# Shield.net
KiCad netlist of a schematic drawn in Altium Designer
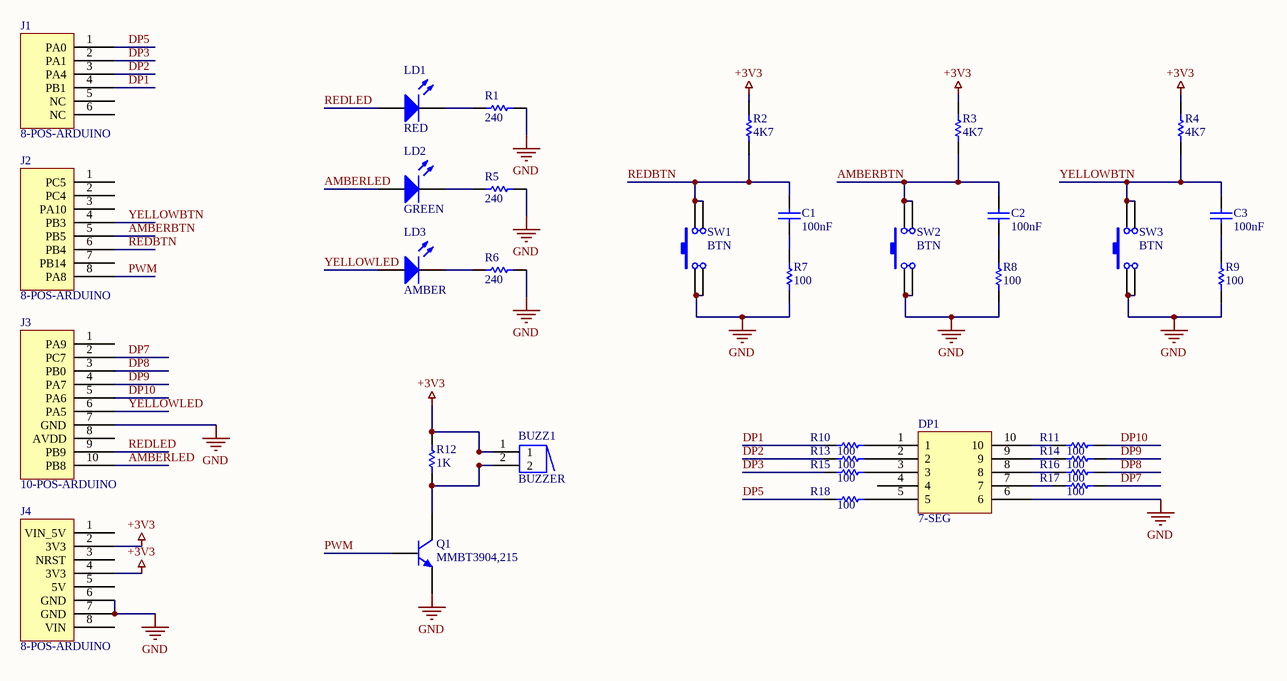
[diagram p0: Shield.SchDoc]

(export (version "E")
  (design (tool "Eeschema 10.0.6"))
  (components
    (comp (ref "BUZZ1")
      (value "BUZZER")
      (footprint "Buzzer")
      (description "AUDIO PIEZO TRANSDUCER 30V TH")
      (fields (field (name "MANUFACTURER") "TDK") (field (name "MANUFACTURER PART NUMBER") "PS1240P02BT"))
      (libsource (lib "Shield") (part "PS1240P02BT"))
    )
    (comp (ref "C1")
      (value "100nF")
      (footprint "CAPC3216X12N")
      (description "CAP CER 0.1UF 50V X7R 1206")
      (fields
        (field (name "MANUFACTURER") "Yageo")
        (field (name "MANUFACTURER PART NUMBER") "CC1206KRX7R9BB104")
      )
      (libsource (lib "Shield") (part "CC1206KRX7R9BB104"))
    )
    (comp (ref "C2")
      (value "100nF")
      (footprint "CAPC3216X12N")
      (description "CAP CER 0.1UF 50V X7R 1206")
      (fields
        (field (name "MANUFACTURER") "Yageo")
        (field (name "MANUFACTURER PART NUMBER") "CC1206KRX7R9BB104")
      )
      (libsource (lib "Shield") (part "CC1206KRX7R9BB104"))
    )
    (comp (ref "C3")
      (value "100nF")
      (footprint "CAPC3216X12N")
      (description "CAP CER 0.1UF 50V X7R 1206")
      (fields
        (field (name "MANUFACTURER") "Yageo")
        (field (name "MANUFACTURER PART NUMBER") "CC1206KRX7R9BB104")
      )
      (libsource (lib "Shield") (part "CC1206KRX7R9BB104"))
    )
    (comp (ref "DP1")
      (value "7-SEG")
      (footprint "7-seg-display")
      (fields
        (field (name "MANUFACTURER") "Inolux")
        (field (name "MANUFACTURER PART NUMBER") "INND-TS40YGCB")
      )
      (libsource (lib "Shield") (part "INND-TS40YGCB"))
    )
    (comp (ref "J1")
      (value "8-POS-ARDUINO")
      (footprint "PIN 6")
      (description "Conn Header Vert 6POS 2.54MM")
      (fields
        (field (name "MANUFACTURER") "Sullins")
        (field (name "MANUFACTURER PART NUMBER") "PREC006SABN-RC")
      )
      (libsource (lib "Shield") (part "PREC006SABN-RC"))
    )
    (comp (ref "J2")
      (value "8-POS-ARDUINO")
      (footprint "PIN 8")
      (description "CONN HEADER VERT 8POS 2.54MM")
      (fields
        (field (name "MANUFACTURER") "Sullins")
        (field (name "MANUFACTURER PART NUMBER") "PREC008SAAN-RC")
      )
      (libsource (lib "Shield") (part "PREC008SAAN-RC"))
    )
    (comp (ref "J3")
      (value "10-POS-ARDUINO")
      (footprint "PIN 10")
      (description "CONN HEADER .100\" SNGL STR 10POS")
      (fields
        (field (name "MANUFACTURER") "Sullins")
        (field (name "MANUFACTURER PART NUMBER") "PREC010SAAN-RC")
      )
      (libsource (lib "Shield") (part "PREC010SAAN-RC"))
    )
    (comp (ref "J4")
      (value "8-POS-ARDUINO")
      (footprint "PIN 8")
      (description "CONN HEADER VERT 8POS 2.54MM")
      (fields
        (field (name "MANUFACTURER") "Sullins")
        (field (name "MANUFACTURER PART NUMBER") "PREC008SAAN-RC")
      )
      (libsource (lib "Shield") (part "PREC008SAAN-RC (2)"))
    )
    (comp (ref "LD1")
      (value "RED")
      (footprint "DIOC3216X21N")
      (description "LED Uni-Color Red 660nm 2-Pin Chip LED T/R")
      (fields
        (field (name "MANUFACTURER") "Vishay Lite-On")
        (field (name "MANUFACTURER PART NUMBER") "LTST-C150CKT")
      )
      (libsource (lib "Shield") (part "LTST-C150CKT"))
    )
    (comp (ref "LD2")
      (value "GREEN")
      (footprint "DIOC3216X21N")
      (description "LED GREEN CLEAR 1206 SMD")
      (fields
        (field (name "MANUFACTURER") "Vishay Lite-On")
        (field (name "MANUFACTURER PART NUMBER") "LTST-C150GKT")
      )
      (libsource (lib "Shield") (part "LTST-C150GKT"))
    )
    (comp (ref "LD3")
      (value "AMBER")
      (footprint "DIOC3216X21N")
      (description "LED AMBER CLEAR 1206 SMD")
      (fields
        (field (name "MANUFACTURER") "Vishay Lite-On")
        (field (name "MANUFACTURER PART NUMBER") "LTST-C150AKT")
      )
      (libsource (lib "Shield") (part "LTST-C150AKT"))
    )
    (comp (ref "Q1")
      (value "MMBT3904,215")
      (footprint "SOT95P230X110-3N")
      (description "TRANS NPN 40V 0.2A SOT23")
      (fields (field (name "MANUFACTURER") "Nexperia"))
      (libsource (lib "Shield") (part "MMBT3904,215"))
    )
    (comp (ref "R1")
      (value "240")
      (footprint "RESC3115X06N")
      (description "Res Thick Film 1206 240 Ohm 1% 0.25W(1/4W) ±100ppm/C Molded SMD Automotive T/R")
      (fields
        (field (name "MANUFACTURER") "Stackpole Electronics")
        (field (name "MANUFACTURER PART NUMBER") "RMCF1206FT240R")
      )
      (libsource (lib "Shield") (part "RMCF1206FT240R"))
    )
    (comp (ref "R2")
      (value "4K7")
      (footprint "RESC3115X06N")
      (description "RES SMD 4.7K OHM 1% 1/4W 1206")
      (fields
        (field (name "MANUFACTURER") "Stackpole Electronics")
        (field (name "MANUFACTURER PART NUMBER") "RMCF1206FT4K70")
      )
      (libsource (lib "Shield") (part "RMCF1206FT4K70"))
    )
    (comp (ref "R3")
      (value "4K7")
      (footprint "RESC3115X06N")
      (description "RES SMD 4.7K OHM 1% 1/4W 1206")
      (fields
        (field (name "MANUFACTURER") "Stackpole Electronics")
        (field (name "MANUFACTURER PART NUMBER") "RMCF1206FT4K70")
      )
      (libsource (lib "Shield") (part "RMCF1206FT4K70"))
    )
    (comp (ref "R4")
      (value "4K7")
      (footprint "RESC3115X06N")
      (description "RES SMD 4.7K OHM 1% 1/4W 1206")
      (fields
        (field (name "MANUFACTURER") "Stackpole Electronics")
        (field (name "MANUFACTURER PART NUMBER") "RMCF1206FT4K70")
      )
      (libsource (lib "Shield") (part "RMCF1206FT4K70"))
    )
    (comp (ref "R5")
      (value "240")
      (footprint "RESC3115X06N")
      (description "Res Thick Film 1206 240 Ohm 1% 0.25W(1/4W) ±100ppm/C Molded SMD Automotive T/R")
      (fields
        (field (name "MANUFACTURER") "Stackpole Electronics")
        (field (name "MANUFACTURER PART NUMBER") "RMCF1206FT240R")
      )
      (libsource (lib "Shield") (part "RMCF1206FT240R"))
    )
    (comp (ref "R6")
      (value "240")
      (footprint "RESC3115X06N")
      (description "Res Thick Film 1206 240 Ohm 1% 0.25W(1/4W) ±100ppm/C Molded SMD Automotive T/R")
      (fields
        (field (name "MANUFACTURER") "Stackpole Electronics")
        (field (name "MANUFACTURER PART NUMBER") "RMCF1206FT240R")
      )
      (libsource (lib "Shield") (part "RMCF1206FT240R"))
    )
    (comp (ref "R7")
      (value "100")
      (footprint "RESC3115X06N")
      (description "RES 100 OHM 1% 1/4W 1206")
      (fields
        (field (name "MANUFACTURER") "Stackpole Electronics")
        (field (name "MANUFACTURER PART NUMBER") "RMCF1206FT100R")
      )
      (libsource (lib "Shield") (part "RMCF1206FT100R"))
    )
    (comp (ref "R8")
      (value "100")
      (footprint "RESC3115X06N")
      (description "RES 100 OHM 1% 1/4W 1206")
      (fields
        (field (name "MANUFACTURER") "Stackpole Electronics")
        (field (name "MANUFACTURER PART NUMBER") "RMCF1206FT100R")
      )
      (libsource (lib "Shield") (part "RMCF1206FT100R"))
    )
    (comp (ref "R9")
      (value "100")
      (footprint "RESC3115X06N")
      (description "RES 100 OHM 1% 1/4W 1206")
      (fields
        (field (name "MANUFACTURER") "Stackpole Electronics")
        (field (name "MANUFACTURER PART NUMBER") "RMCF1206FT100R")
      )
      (libsource (lib "Shield") (part "RMCF1206FT100R"))
    )
    (comp (ref "R10")
      (value "100")
      (footprint "RESC3115X06N")
      (description "RES 100 OHM 1% 1/4W 1206")
      (fields
        (field (name "MANUFACTURER") "Stackpole Electronics")
        (field (name "MANUFACTURER PART NUMBER") "RMCF1206FT100R")
      )
      (libsource (lib "Shield") (part "RMCF1206FT100R"))
    )
    (comp (ref "R11")
      (value "100")
      (footprint "RESC3115X06N")
      (description "RES 100 OHM 1% 1/4W 1206")
      (fields
        (field (name "MANUFACTURER") "Stackpole Electronics")
        (field (name "MANUFACTURER PART NUMBER") "RMCF1206FT100R")
      )
      (libsource (lib "Shield") (part "RMCF1206FT100R"))
    )
    (comp (ref "R12")
      (value "1K")
      (footprint "RESC3115X06N")
      (description "RES 1K OHM 1% 1/2W 1206")
      (fields
        (field (name "MANUFACTURER") "Stackpole Electronics")
        (field (name "MANUFACTURER PART NUMBER") "RNCP1206FTD1K00")
      )
      (libsource (lib "Shield") (part "RNCP1206FTD1K00"))
    )
    (comp (ref "R13")
      (value "100")
      (footprint "RESC3115X06N")
      (description "RES 100 OHM 1% 1/4W 1206")
      (fields
        (field (name "MANUFACTURER") "Stackpole Electronics")
        (field (name "MANUFACTURER PART NUMBER") "RMCF1206FT100R")
      )
      (libsource (lib "Shield") (part "RMCF1206FT100R"))
    )
    (comp (ref "R14")
      (value "100")
      (footprint "RESC3115X06N")
      (description "RES 100 OHM 1% 1/4W 1206")
      (fields
        (field (name "MANUFACTURER") "Stackpole Electronics")
        (field (name "MANUFACTURER PART NUMBER") "RMCF1206FT100R")
      )
      (libsource (lib "Shield") (part "RMCF1206FT100R"))
    )
    (comp (ref "R15")
      (value "100")
      (footprint "RESC3115X06N")
      (description "RES 100 OHM 1% 1/4W 1206")
      (fields
        (field (name "MANUFACTURER") "Stackpole Electronics")
        (field (name "MANUFACTURER PART NUMBER") "RMCF1206FT100R")
      )
      (libsource (lib "Shield") (part "RMCF1206FT100R"))
    )
    (comp (ref "R16")
      (value "100")
      (footprint "RESC3115X06N")
      (description "RES 100 OHM 1% 1/4W 1206")
      (fields
        (field (name "MANUFACTURER") "Stackpole Electronics")
        (field (name "MANUFACTURER PART NUMBER") "RMCF1206FT100R")
      )
      (libsource (lib "Shield") (part "RMCF1206FT100R"))
    )
    (comp (ref "R17")
      (value "100")
      (footprint "RESC3115X06N")
      (description "RES 100 OHM 1% 1/4W 1206")
      (fields
        (field (name "MANUFACTURER") "Stackpole Electronics")
        (field (name "MANUFACTURER PART NUMBER") "RMCF1206FT100R")
      )
      (libsource (lib "Shield") (part "RMCF1206FT100R"))
    )
    (comp (ref "R18")
      (value "100")
      (footprint "RESC3115X06N")
      (description "RES 100 OHM 1% 1/4W 1206")
      (fields
        (field (name "MANUFACTURER") "Stackpole Electronics")
        (field (name "MANUFACTURER PART NUMBER") "RMCF1206FT100R")
      )
      (libsource (lib "Shield") (part "RMCF1206FT100R"))
    )
    (comp (ref "SW1")
      (value "BTN")
      (footprint "Button")
      (description "INWALL LENS COVER , WHITE , 6 (")
      (fields
        (field (name "MANUFACTURER") "ITT C&K")
        (field (name "MANUFACTURER PART NUMBER") "PTS647SK70SMTR2LFS")
      )
      (libsource (lib "Shield") (part "PTS647SK70SMTR2LFS"))
    )
    (comp (ref "SW2")
      (value "BTN")
      (footprint "Button")
      (description "INWALL LENS COVER , WHITE , 6 (")
      (fields
        (field (name "MANUFACTURER") "ITT C&K")
        (field (name "MANUFACTURER PART NUMBER") "PTS647SK70SMTR2LFS")
      )
      (libsource (lib "Shield") (part "PTS647SK70SMTR2LFS"))
    )
    (comp (ref "SW3")
      (value "BTN")
      (footprint "Button")
      (description "INWALL LENS COVER , WHITE , 6 (")
      (fields
        (field (name "MANUFACTURER") "ITT C&K")
        (field (name "MANUFACTURER PART NUMBER") "PTS647SK70SMTR2LFS")
      )
      (libsource (lib "Shield") (part "PTS647SK70SMTR2LFS"))
    )
  )
  (nets
    (net (code "1") (name "+3V3") (class "Default")
      (node (ref "BUZZ1") (pin "1") (pinfunction "1_1") (pintype "passive"))
      (node (ref "J4") (pin "2") (pinfunction "3V3_2") (pintype "passive"))
      (node (ref "J4") (pin "4") (pinfunction "3V3_4") (pintype "passive"))
      (node (ref "R12") (pin "2") (pinfunction "2_2") (pintype "passive"))
      (node (ref "R2") (pin "2") (pinfunction "2_2") (pintype "passive"))
      (node (ref "R3") (pin "2") (pinfunction "2_2") (pintype "passive"))
      (node (ref "R4") (pin "2") (pinfunction "2_2") (pintype "passive"))
    )
    (net (code "2") (name "/AMBERBTN") (class "Default")
      (node (ref "C2") (pin "2") (pinfunction "2_2") (pintype "passive"))
      (node (ref "J2") (pin "5") (pinfunction "PB5_5") (pintype "passive"))
      (node (ref "R3") (pin "1") (pinfunction "1_1") (pintype "passive"))
      (node (ref "SW2") (pin "3") (pinfunction "2_3") (pintype "passive"))
      (node (ref "SW2") (pin "4") (pinfunction "3_4") (pintype "passive"))
    )
    (net (code "3") (name "/AMBERLED") (class "Default")
      (node (ref "J3") (pin "10") (pinfunction "PB8_10") (pintype "passive"))
      (node (ref "LD2") (pin "1") (pinfunction "A_1") (pintype "passive"))
    )
    (net (code "4") (name "/DP1") (class "Default")
      (node (ref "J1") (pin "4") (pinfunction "PB1_4") (pintype "passive"))
      (node (ref "R10") (pin "2") (pinfunction "2_2") (pintype "passive"))
    )
    (net (code "5") (name "/DP2") (class "Default")
      (node (ref "J1") (pin "3") (pinfunction "PA4_3") (pintype "passive"))
      (node (ref "R13") (pin "2") (pinfunction "2_2") (pintype "passive"))
    )
    (net (code "6") (name "/DP3") (class "Default")
      (node (ref "J1") (pin "2") (pinfunction "PA1_2") (pintype "passive"))
      (node (ref "R15") (pin "2") (pinfunction "2_2") (pintype "passive"))
    )
    (net (code "7") (name "/DP5") (class "Default")
      (node (ref "J1") (pin "1") (pinfunction "PA0_1") (pintype "passive"))
      (node (ref "R18") (pin "2") (pinfunction "2_2") (pintype "passive"))
    )
    (net (code "8") (name "/DP7") (class "Default")
      (node (ref "J3") (pin "2") (pinfunction "PC7_2") (pintype "passive"))
      (node (ref "R17") (pin "1") (pinfunction "1_1") (pintype "passive"))
    )
    (net (code "9") (name "/DP8") (class "Default")
      (node (ref "J3") (pin "3") (pinfunction "PB0_3") (pintype "passive"))
      (node (ref "R16") (pin "1") (pinfunction "1_1") (pintype "passive"))
    )
    (net (code "10") (name "/DP9") (class "Default")
      (node (ref "J3") (pin "4") (pinfunction "PA7_4") (pintype "passive"))
      (node (ref "R14") (pin "1") (pinfunction "1_1") (pintype "passive"))
    )
    (net (code "11") (name "/DP10") (class "Default")
      (node (ref "J3") (pin "5") (pinfunction "PA6_5") (pintype "passive"))
      (node (ref "R11") (pin "1") (pinfunction "1_1") (pintype "passive"))
    )
    (net (code "12") (name "/PWM") (class "Default")
      (node (ref "J2") (pin "8") (pinfunction "PA8_8") (pintype "passive"))
      (node (ref "Q1") (pin "1") (pinfunction "B_1") (pintype "passive"))
    )
    (net (code "13") (name "/REDBTN") (class "Default")
      (node (ref "C1") (pin "2") (pinfunction "2_2") (pintype "passive"))
      (node (ref "J2") (pin "6") (pinfunction "PB4_6") (pintype "passive"))
      (node (ref "R2") (pin "1") (pinfunction "1_1") (pintype "passive"))
      (node (ref "SW1") (pin "3") (pinfunction "2_3") (pintype "passive"))
      (node (ref "SW1") (pin "4") (pinfunction "3_4") (pintype "passive"))
    )
    (net (code "14") (name "/REDLED") (class "Default")
      (node (ref "J3") (pin "9") (pinfunction "PB9_9") (pintype "passive"))
      (node (ref "LD1") (pin "1") (pinfunction "A_1") (pintype "passive"))
    )
    (net (code "15") (name "/YELLOWBTN") (class "Default")
      (node (ref "C3") (pin "2") (pinfunction "2_2") (pintype "passive"))
      (node (ref "J2") (pin "4") (pinfunction "PB3_4") (pintype "passive"))
      (node (ref "R4") (pin "1") (pinfunction "1_1") (pintype "passive"))
      (node (ref "SW3") (pin "3") (pinfunction "2_3") (pintype "passive"))
      (node (ref "SW3") (pin "4") (pinfunction "3_4") (pintype "passive"))
    )
    (net (code "16") (name "/YELLOWLED") (class "Default")
      (node (ref "J3") (pin "6") (pinfunction "PA5_6") (pintype "passive"))
      (node (ref "LD3") (pin "1") (pinfunction "A_1") (pintype "passive"))
    )
    (net (code "17") (name "GND") (class "Default")
      (node (ref "DP1") (pin "6") (pinfunction "6_6") (pintype "passive"))
      (node (ref "J3") (pin "7") (pinfunction "GND_7") (pintype "passive"))
      (node (ref "J4") (pin "6") (pinfunction "GND_6") (pintype "passive"))
      (node (ref "J4") (pin "7") (pinfunction "GND_7") (pintype "passive"))
      (node (ref "Q1") (pin "2") (pinfunction "E_2") (pintype "passive"))
      (node (ref "R1") (pin "2") (pinfunction "2_2") (pintype "passive"))
      (node (ref "R5") (pin "2") (pinfunction "2_2") (pintype "passive"))
      (node (ref "R6") (pin "2") (pinfunction "2_2") (pintype "passive"))
      (node (ref "R7") (pin "1") (pinfunction "1_1") (pintype "passive"))
      (node (ref "R8") (pin "1") (pinfunction "1_1") (pintype "passive"))
      (node (ref "R9") (pin "1") (pinfunction "1_1") (pintype "passive"))
      (node (ref "SW1") (pin "1") (pinfunction "1_1") (pintype "passive"))
      (node (ref "SW1") (pin "2") (pinfunction "1_2") (pintype "passive"))
      (node (ref "SW2") (pin "1") (pinfunction "1_1") (pintype "passive"))
      (node (ref "SW2") (pin "2") (pinfunction "1_2") (pintype "passive"))
      (node (ref "SW3") (pin "1") (pinfunction "1_1") (pintype "passive"))
      (node (ref "SW3") (pin "2") (pinfunction "1_2") (pintype "passive"))
    )
    (net (code "18") (name "Net-(C1-Pad1)") (class "Default")
      (node (ref "C1") (pin "1") (pinfunction "1_1") (pintype "passive"))
      (node (ref "R7") (pin "2") (pinfunction "2_2") (pintype "passive"))
    )
    (net (code "19") (name "Net-(C2-Pad1)") (class "Default")
      (node (ref "C2") (pin "1") (pinfunction "1_1") (pintype "passive"))
      (node (ref "R8") (pin "2") (pinfunction "2_2") (pintype "passive"))
    )
    (net (code "20") (name "Net-(C3-Pad1)") (class "Default")
      (node (ref "C3") (pin "1") (pinfunction "1_1") (pintype "passive"))
      (node (ref "R9") (pin "2") (pinfunction "2_2") (pintype "passive"))
    )
    (net (code "21") (name "Net-(DP1-Pad1)") (class "Default")
      (node (ref "DP1") (pin "1") (pinfunction "1_1") (pintype "passive"))
      (node (ref "R10") (pin "1") (pinfunction "1_1") (pintype "passive"))
    )
    (net (code "22") (name "Net-(DP1-Pad2)") (class "Default")
      (node (ref "DP1") (pin "2") (pinfunction "2_2") (pintype "passive"))
      (node (ref "R13") (pin "1") (pinfunction "1_1") (pintype "passive"))
    )
    (net (code "23") (name "Net-(DP1-Pad3)") (class "Default")
      (node (ref "DP1") (pin "3") (pinfunction "3_3") (pintype "passive"))
      (node (ref "R15") (pin "1") (pinfunction "1_1") (pintype "passive"))
    )
    (net (code "24") (name "Net-(DP1-Pad5)") (class "Default")
      (node (ref "DP1") (pin "5") (pinfunction "5_5") (pintype "passive"))
      (node (ref "R18") (pin "1") (pinfunction "1_1") (pintype "passive"))
    )
    (net (code "25") (name "Net-(DP1-Pad7)") (class "Default")
      (node (ref "DP1") (pin "7") (pinfunction "7_7") (pintype "passive"))
      (node (ref "R17") (pin "2") (pinfunction "2_2") (pintype "passive"))
    )
    (net (code "26") (name "Net-(DP1-Pad8)") (class "Default")
      (node (ref "DP1") (pin "8") (pinfunction "8_8") (pintype "passive"))
      (node (ref "R16") (pin "2") (pinfunction "2_2") (pintype "passive"))
    )
    (net (code "27") (name "Net-(DP1-Pad9)") (class "Default")
      (node (ref "DP1") (pin "9") (pinfunction "9_9") (pintype "passive"))
      (node (ref "R14") (pin "2") (pinfunction "2_2") (pintype "passive"))
    )
    (net (code "28") (name "Net-(DP1-Pad10)") (class "Default")
      (node (ref "DP1") (pin "10") (pinfunction "10_10") (pintype "passive"))
      (node (ref "R11") (pin "2") (pinfunction "2_2") (pintype "passive"))
    )
    (net (code "29") (name "Net-(LD1-K)") (class "Default")
      (node (ref "LD1") (pin "2") (pinfunction "K_2") (pintype "passive"))
      (node (ref "R1") (pin "1") (pinfunction "1_1") (pintype "passive"))
    )
    (net (code "30") (name "Net-(LD2-K)") (class "Default")
      (node (ref "LD2") (pin "2") (pinfunction "K_2") (pintype "passive"))
      (node (ref "R5") (pin "1") (pinfunction "1_1") (pintype "passive"))
    )
    (net (code "31") (name "Net-(LD3-K)") (class "Default")
      (node (ref "LD3") (pin "2") (pinfunction "K_2") (pintype "passive"))
      (node (ref "R6") (pin "1") (pinfunction "1_1") (pintype "passive"))
    )
    (net (code "32") (name "Net-(Q1-C)") (class "Default")
      (node (ref "BUZZ1") (pin "2") (pinfunction "2_2") (pintype "passive"))
      (node (ref "Q1") (pin "3") (pinfunction "C_3") (pintype "passive"))
      (node (ref "R12") (pin "1") (pinfunction "1_1") (pintype "passive"))
    )
    (net (code "33") (name "unconnected-(DP1-Pad4)") (class "Default")
      (node (ref "DP1") (pin "4") (pinfunction "4_4") (pintype "passive"))
    )
    (net (code "34") (name "unconnected-(J1-NC-Pad5)") (class "Default")
      (node (ref "J1") (pin "5") (pinfunction "NC_5") (pintype "passive"))
    )
    (net (code "35") (name "unconnected-(J1-NC-Pad6)") (class "Default")
      (node (ref "J1") (pin "6") (pinfunction "NC_6") (pintype "passive"))
    )
    (net (code "36") (name "unconnected-(J2-PA10-Pad3)") (class "Default")
      (node (ref "J2") (pin "3") (pinfunction "PA10_3") (pintype "passive"))
    )
    (net (code "37") (name "unconnected-(J2-PB14-Pad7)") (class "Default")
      (node (ref "J2") (pin "7") (pinfunction "PB14_7") (pintype "passive"))
    )
    (net (code "38") (name "unconnected-(J2-PC4-Pad2)") (class "Default")
      (node (ref "J2") (pin "2") (pinfunction "PC4_2") (pintype "passive"))
    )
    (net (code "39") (name "unconnected-(J2-PC5-Pad1)") (class "Default")
      (node (ref "J2") (pin "1") (pinfunction "PC5_1") (pintype "passive"))
    )
    (net (code "40") (name "unconnected-(J3-AVDD-Pad8)") (class "Default")
      (node (ref "J3") (pin "8") (pinfunction "AVDD_8") (pintype "passive"))
    )
    (net (code "41") (name "unconnected-(J3-PA9-Pad1)") (class "Default")
      (node (ref "J3") (pin "1") (pinfunction "PA9_1") (pintype "passive"))
    )
    (net (code "42") (name "unconnected-(J4-5V-Pad5)") (class "Default")
      (node (ref "J4") (pin "5") (pinfunction "5V_5") (pintype "passive"))
    )
    (net (code "43") (name "unconnected-(J4-NRST-Pad3)") (class "Default")
      (node (ref "J4") (pin "3") (pinfunction "NRST_3") (pintype "passive"))
    )
    (net (code "44") (name "unconnected-(J4-VIN-Pad8)") (class "Default")
      (node (ref "J4") (pin "8") (pinfunction "VIN_8") (pintype "passive"))
    )
    (net (code "45") (name "unconnected-(J4-VIN_5V-Pad1)") (class "Default")
      (node (ref "J4") (pin "1") (pinfunction "VIN_5V_1") (pintype "passive"))
    )
  )
)
